# 4-Fuses.net
KiCad netlist of a schematic drawn in Altium Designer
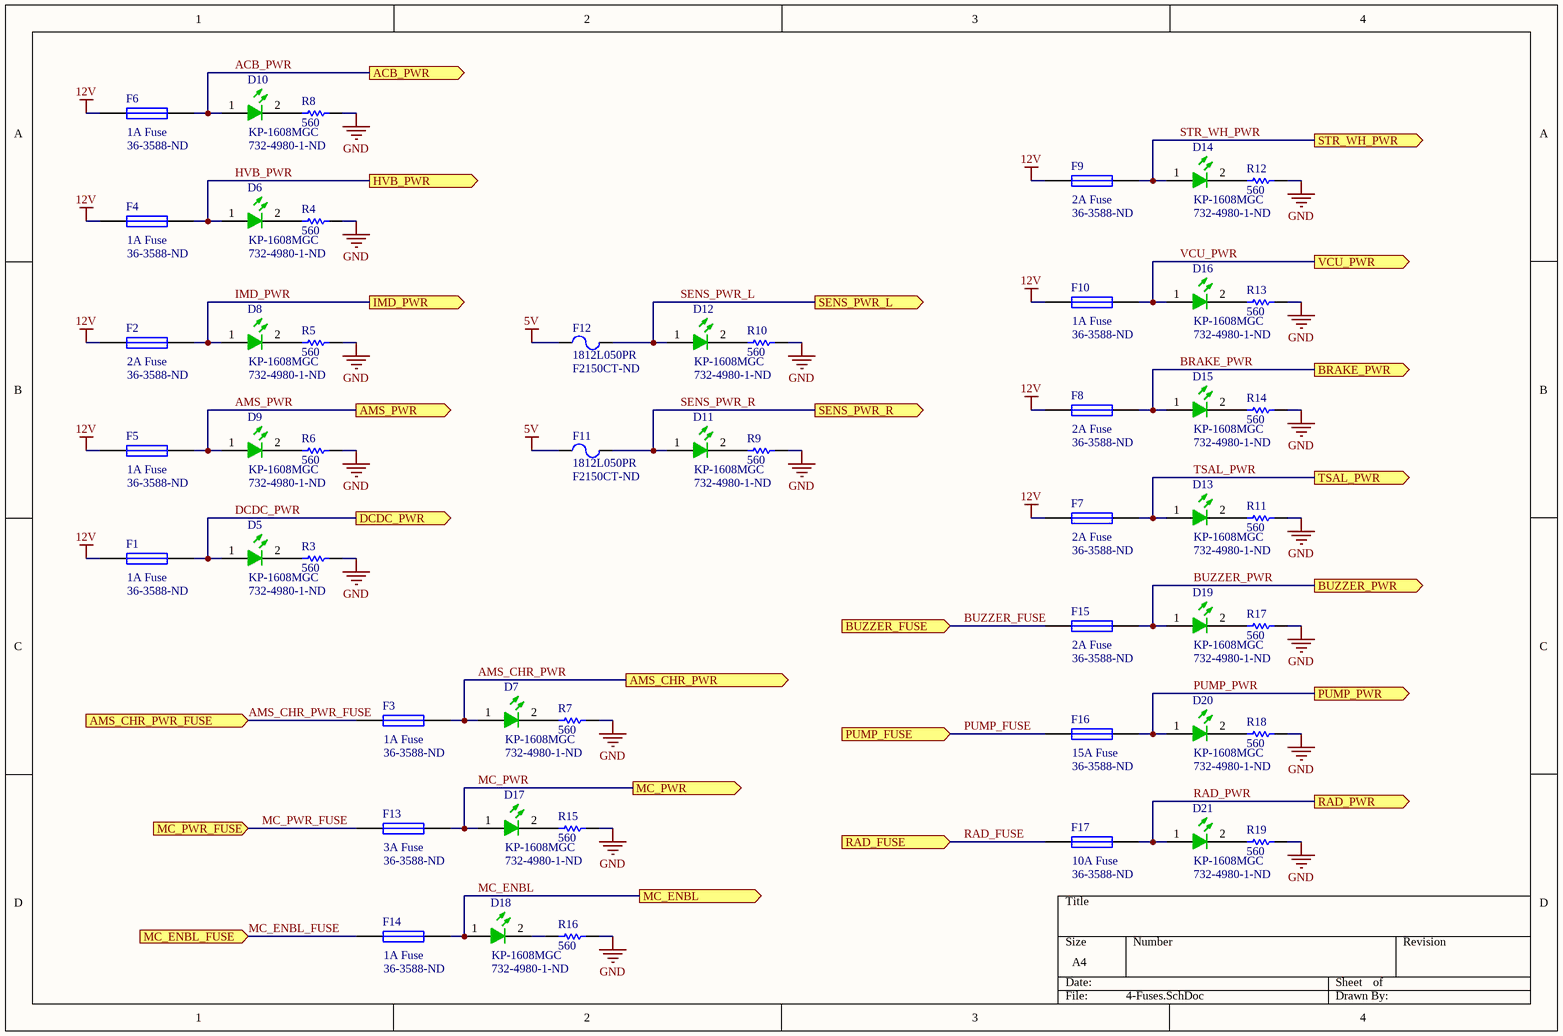
[diagram p0: 4-Fuses.SchDoc]

(export (version "E")
  (design (tool "Eeschema 10.0.6"))
  (components
    (comp (ref "D5")
      (value "KP-1608MGC")
      (footprint "KING-0603LED_GREEN_V")
      (description "LED, SMT, 0603(1608), 1.1mm thickness, Green")
      (fields
        (field (name "MANUFACTURER") "Kingbright")
        (field (name "SUPPLIER PART NUMBER 1") "732-4980-1-ND")
      )
      (libsource (lib "Altium Content Vault") (part "KING-LED-GREEN-A1K2-2"))
    )
    (comp (ref "D6")
      (value "KP-1608MGC")
      (footprint "KING-0603LED_GREEN_V")
      (description "LED, SMT, 0603(1608), 1.1mm thickness, Green")
      (fields
        (field (name "MANUFACTURER") "Kingbright")
        (field (name "SUPPLIER PART NUMBER 1") "732-4980-1-ND")
      )
      (libsource (lib "Altium Content Vault") (part "KING-LED-GREEN-A1K2-2"))
    )
    (comp (ref "D7")
      (value "KP-1608MGC")
      (footprint "KING-0603LED_GREEN_V")
      (description "LED, SMT, 0603(1608), 1.1mm thickness, Green")
      (fields
        (field (name "MANUFACTURER") "Kingbright")
        (field (name "SUPPLIER PART NUMBER 1") "732-4980-1-ND")
      )
      (libsource (lib "Altium Content Vault") (part "KING-LED-GREEN-A1K2-2"))
    )
    (comp (ref "D8")
      (value "KP-1608MGC")
      (footprint "KING-0603LED_GREEN_V")
      (description "LED, SMT, 0603(1608), 1.1mm thickness, Green")
      (fields
        (field (name "MANUFACTURER") "Kingbright")
        (field (name "SUPPLIER PART NUMBER 1") "732-4980-1-ND")
      )
      (libsource (lib "Altium Content Vault") (part "KING-LED-GREEN-A1K2-2"))
    )
    (comp (ref "D9")
      (value "KP-1608MGC")
      (footprint "KING-0603LED_GREEN_V")
      (description "LED, SMT, 0603(1608), 1.1mm thickness, Green")
      (fields
        (field (name "MANUFACTURER") "Kingbright")
        (field (name "SUPPLIER PART NUMBER 1") "732-4980-1-ND")
      )
      (libsource (lib "Altium Content Vault") (part "KING-LED-GREEN-A1K2-2"))
    )
    (comp (ref "D10")
      (value "KP-1608MGC")
      (footprint "KING-0603LED_GREEN_V")
      (description "LED, SMT, 0603(1608), 1.1mm thickness, Green")
      (fields
        (field (name "MANUFACTURER") "Kingbright")
        (field (name "SUPPLIER PART NUMBER 1") "732-4980-1-ND")
      )
      (libsource (lib "Altium Content Vault") (part "KING-LED-GREEN-A1K2-2"))
    )
    (comp (ref "D11")
      (value "KP-1608MGC")
      (footprint "KING-0603LED_GREEN_V")
      (description "LED, SMT, 0603(1608), 1.1mm thickness, Green")
      (fields
        (field (name "MANUFACTURER") "Kingbright")
        (field (name "SUPPLIER PART NUMBER 1") "732-4980-1-ND")
      )
      (libsource (lib "Altium Content Vault") (part "KING-LED-GREEN-A1K2-2"))
    )
    (comp (ref "D12")
      (value "KP-1608MGC")
      (footprint "KING-0603LED_GREEN_V")
      (description "LED, SMT, 0603(1608), 1.1mm thickness, Green")
      (fields
        (field (name "MANUFACTURER") "Kingbright")
        (field (name "SUPPLIER PART NUMBER 1") "732-4980-1-ND")
      )
      (libsource (lib "Altium Content Vault") (part "KING-LED-GREEN-A1K2-2"))
    )
    (comp (ref "D13")
      (value "KP-1608MGC")
      (footprint "KING-0603LED_GREEN_V")
      (description "LED, SMT, 0603(1608), 1.1mm thickness, Green")
      (fields
        (field (name "MANUFACTURER") "Kingbright")
        (field (name "SUPPLIER PART NUMBER 1") "732-4980-1-ND")
      )
      (libsource (lib "Altium Content Vault") (part "KING-LED-GREEN-A1K2-2"))
    )
    (comp (ref "D14")
      (value "KP-1608MGC")
      (footprint "KING-0603LED_GREEN_V")
      (description "LED, SMT, 0603(1608), 1.1mm thickness, Green")
      (fields
        (field (name "MANUFACTURER") "Kingbright")
        (field (name "SUPPLIER PART NUMBER 1") "732-4980-1-ND")
      )
      (libsource (lib "Altium Content Vault") (part "KING-LED-GREEN-A1K2-2"))
    )
    (comp (ref "D15")
      (value "KP-1608MGC")
      (footprint "KING-0603LED_GREEN_V")
      (description "LED, SMT, 0603(1608), 1.1mm thickness, Green")
      (fields
        (field (name "MANUFACTURER") "Kingbright")
        (field (name "SUPPLIER PART NUMBER 1") "732-4980-1-ND")
      )
      (libsource (lib "Altium Content Vault") (part "KING-LED-GREEN-A1K2-2"))
    )
    (comp (ref "D16")
      (value "KP-1608MGC")
      (footprint "KING-0603LED_GREEN_V")
      (description "LED, SMT, 0603(1608), 1.1mm thickness, Green")
      (fields
        (field (name "MANUFACTURER") "Kingbright")
        (field (name "SUPPLIER PART NUMBER 1") "732-4980-1-ND")
      )
      (libsource (lib "Altium Content Vault") (part "KING-LED-GREEN-A1K2-2"))
    )
    (comp (ref "D17")
      (value "KP-1608MGC")
      (footprint "KING-0603LED_GREEN_V")
      (description "LED, SMT, 0603(1608), 1.1mm thickness, Green")
      (fields
        (field (name "MANUFACTURER") "Kingbright")
        (field (name "SUPPLIER PART NUMBER 1") "732-4980-1-ND")
      )
      (libsource (lib "Altium Content Vault") (part "KING-LED-GREEN-A1K2-2"))
    )
    (comp (ref "D18")
      (value "KP-1608MGC")
      (footprint "KING-0603LED_GREEN_V")
      (description "LED, SMT, 0603(1608), 1.1mm thickness, Green")
      (fields
        (field (name "MANUFACTURER") "Kingbright")
        (field (name "SUPPLIER PART NUMBER 1") "732-4980-1-ND")
      )
      (libsource (lib "Altium Content Vault") (part "KING-LED-GREEN-A1K2-2"))
    )
    (comp (ref "D19")
      (value "KP-1608MGC")
      (footprint "KING-0603LED_GREEN_V")
      (description "LED, SMT, 0603(1608), 1.1mm thickness, Green")
      (fields
        (field (name "MANUFACTURER") "Kingbright")
        (field (name "SUPPLIER PART NUMBER 1") "732-4980-1-ND")
      )
      (libsource (lib "Altium Content Vault") (part "KING-LED-GREEN-A1K2-2"))
    )
    (comp (ref "D20")
      (value "KP-1608MGC")
      (footprint "KING-0603LED_GREEN_V")
      (description "LED, SMT, 0603(1608), 1.1mm thickness, Green")
      (fields
        (field (name "MANUFACTURER") "Kingbright")
        (field (name "SUPPLIER PART NUMBER 1") "732-4980-1-ND")
      )
      (libsource (lib "Altium Content Vault") (part "KING-LED-GREEN-A1K2-2"))
    )
    (comp (ref "D21")
      (value "KP-1608MGC")
      (footprint "KING-0603LED_GREEN_V")
      (description "LED, SMT, 0603(1608), 1.1mm thickness, Green")
      (fields
        (field (name "MANUFACTURER") "Kingbright")
        (field (name "SUPPLIER PART NUMBER 1") "732-4980-1-ND")
      )
      (libsource (lib "Altium Content Vault") (part "KING-LED-GREEN-A1K2-2"))
    )
    (comp (ref "F1")
      (value "1A Fuse")
      (footprint "FUSE 3588 Holder")
      (description "Fuse")
      (fields
        (field (name "SUPPLIER PART NUMBER 1") "36-3588-ND")
        (field (name "PUBLISHER") "Altium Limited")
      )
      (libsource (lib "Power_PCB") (part "Fuse 1"))
    )
    (comp (ref "F2")
      (value "2A Fuse")
      (footprint "FUSE 3588 Holder")
      (description "Fuse")
      (fields
        (field (name "SUPPLIER PART NUMBER 1") "36-3588-ND")
        (field (name "PUBLISHER") "Altium Limited")
      )
      (libsource (lib "Power_PCB") (part "Fuse 1"))
    )
    (comp (ref "F3")
      (value "1A Fuse")
      (footprint "FUSE 3588 Holder")
      (description "Fuse")
      (fields
        (field (name "SUPPLIER PART NUMBER 1") "36-3588-ND")
        (field (name "PUBLISHER") "Altium Limited")
      )
      (libsource (lib "Power_PCB") (part "Fuse 1"))
    )
    (comp (ref "F4")
      (value "1A Fuse")
      (footprint "FUSE 3588 Holder")
      (description "Fuse")
      (fields
        (field (name "SUPPLIER PART NUMBER 1") "36-3588-ND")
        (field (name "PUBLISHER") "Altium Limited")
      )
      (libsource (lib "Power_PCB") (part "Fuse 1"))
    )
    (comp (ref "F5")
      (value "1A Fuse")
      (footprint "FUSE 3588 Holder")
      (description "Fuse")
      (fields
        (field (name "SUPPLIER PART NUMBER 1") "36-3588-ND")
        (field (name "PUBLISHER") "Altium Limited")
      )
      (libsource (lib "Power_PCB") (part "Fuse 1"))
    )
    (comp (ref "F6")
      (value "1A Fuse")
      (footprint "FUSE 3588 Holder")
      (description "Fuse")
      (fields
        (field (name "SUPPLIER PART NUMBER 1") "36-3588-ND")
        (field (name "PUBLISHER") "Altium Limited")
      )
      (libsource (lib "Power_PCB") (part "Fuse 1"))
    )
    (comp (ref "F7")
      (value "2A Fuse")
      (footprint "FUSE 3588 Holder")
      (description "Fuse")
      (fields
        (field (name "SUPPLIER PART NUMBER 1") "36-3588-ND")
        (field (name "PUBLISHER") "Altium Limited")
      )
      (libsource (lib "Power_PCB") (part "Fuse 1"))
    )
    (comp (ref "F8")
      (value "2A Fuse")
      (footprint "FUSE 3588 Holder")
      (description "Fuse")
      (fields
        (field (name "SUPPLIER PART NUMBER 1") "36-3588-ND")
        (field (name "PUBLISHER") "Altium Limited")
      )
      (libsource (lib "Power_PCB") (part "Fuse 1"))
    )
    (comp (ref "F9")
      (value "2A Fuse")
      (footprint "FUSE 3588 Holder")
      (description "Fuse")
      (fields
        (field (name "SUPPLIER PART NUMBER 1") "36-3588-ND")
        (field (name "PUBLISHER") "Altium Limited")
      )
      (libsource (lib "Power_PCB") (part "Fuse 1"))
    )
    (comp (ref "F10")
      (value "1A Fuse")
      (footprint "FUSE 3588 Holder")
      (description "Fuse")
      (fields
        (field (name "SUPPLIER PART NUMBER 1") "36-3588-ND")
        (field (name "PUBLISHER") "Altium Limited")
      )
      (libsource (lib "Power_PCB") (part "Fuse 1"))
    )
    (comp (ref "F11")
      (value "1812L050PR")
      (footprint "LFUS-1812L050_V")
      (fields (field (name "TOLERANCE") "1%") (field (name "SUPPLIER PART NUMBER 1") "F2150CT-ND"))
      (libsource (lib "Power_PCB") (part "CMP-1700-00002-1"))
    )
    (comp (ref "F12")
      (value "1812L050PR")
      (footprint "LFUS-1812L050_V")
      (fields (field (name "TOLERANCE") "1%") (field (name "SUPPLIER PART NUMBER 1") "F2150CT-ND"))
      (libsource (lib "Power_PCB") (part "CMP-1700-00002-1"))
    )
    (comp (ref "F13")
      (value "3A Fuse")
      (footprint "FUSE 3588 Holder")
      (description "Fuse")
      (fields
        (field (name "SUPPLIER PART NUMBER 1") "36-3588-ND")
        (field (name "PUBLISHER") "Altium Limited")
      )
      (libsource (lib "Power_PCB") (part "Fuse 1"))
    )
    (comp (ref "F14")
      (value "1A Fuse")
      (footprint "FUSE 3588 Holder")
      (description "Fuse")
      (fields
        (field (name "SUPPLIER PART NUMBER 1") "36-3588-ND")
        (field (name "PUBLISHER") "Altium Limited")
      )
      (libsource (lib "Power_PCB") (part "Fuse 1"))
    )
    (comp (ref "F15")
      (value "2A Fuse")
      (footprint "FUSE 3588 Holder")
      (description "Fuse")
      (fields
        (field (name "SUPPLIER PART NUMBER 1") "36-3588-ND")
        (field (name "PUBLISHER") "Altium Limited")
      )
      (libsource (lib "Power_PCB") (part "Fuse 1"))
    )
    (comp (ref "F16")
      (value "15A Fuse")
      (footprint "FUSE 3588 Holder")
      (description "Fuse")
      (fields
        (field (name "SUPPLIER PART NUMBER 1") "36-3588-ND")
        (field (name "PUBLISHER") "Altium Limited")
      )
      (libsource (lib "Power_PCB") (part "Fuse 1"))
    )
    (comp (ref "F17")
      (value "10A Fuse")
      (footprint "FUSE 3588 Holder")
      (description "Fuse")
      (fields
        (field (name "SUPPLIER PART NUMBER 1") "36-3588-ND")
        (field (name "PUBLISHER") "Altium Limited")
      )
      (libsource (lib "Power_PCB") (part "Fuse 1"))
    )
    (comp (ref "R3")
      (value "560")
      (footprint "RESC0603(1608)_L")
      (description "0603 (1608 Metric) Chip Resistor")
      (libsource (lib "Altium Content Vault") (part "RES_3"))
    )
    (comp (ref "R4")
      (value "560")
      (footprint "RESC0603(1608)_L")
      (description "0603 (1608 Metric) Chip Resistor")
      (libsource (lib "Altium Content Vault") (part "RES_3"))
    )
    (comp (ref "R5")
      (value "560")
      (footprint "RESC0603(1608)_L")
      (description "0603 (1608 Metric) Chip Resistor")
      (libsource (lib "Altium Content Vault") (part "RES_3"))
    )
    (comp (ref "R6")
      (value "560")
      (footprint "RESC0603(1608)_L")
      (description "0603 (1608 Metric) Chip Resistor")
      (libsource (lib "Altium Content Vault") (part "RES_3"))
    )
    (comp (ref "R7")
      (value "560")
      (footprint "RESC0603(1608)_L")
      (description "0603 (1608 Metric) Chip Resistor")
      (libsource (lib "Altium Content Vault") (part "RES_3"))
    )
    (comp (ref "R8")
      (value "560")
      (footprint "RESC0603(1608)_L")
      (description "0603 (1608 Metric) Chip Resistor")
      (libsource (lib "Altium Content Vault") (part "RES_3"))
    )
    (comp (ref "R9")
      (value "560")
      (footprint "RESC0603(1608)_L")
      (description "0603 (1608 Metric) Chip Resistor")
      (libsource (lib "Altium Content Vault") (part "RES_3"))
    )
    (comp (ref "R10")
      (value "560")
      (footprint "RESC0603(1608)_L")
      (description "0603 (1608 Metric) Chip Resistor")
      (libsource (lib "Altium Content Vault") (part "RES_3"))
    )
    (comp (ref "R11")
      (value "560")
      (footprint "RESC0603(1608)_L")
      (description "0603 (1608 Metric) Chip Resistor")
      (libsource (lib "Altium Content Vault") (part "RES_3"))
    )
    (comp (ref "R12")
      (value "560")
      (footprint "RESC0603(1608)_L")
      (description "0603 (1608 Metric) Chip Resistor")
      (libsource (lib "Altium Content Vault") (part "RES_3"))
    )
    (comp (ref "R13")
      (value "560")
      (footprint "RESC0603(1608)_L")
      (description "0603 (1608 Metric) Chip Resistor")
      (libsource (lib "Altium Content Vault") (part "RES_3"))
    )
    (comp (ref "R14")
      (value "560")
      (footprint "RESC0603(1608)_L")
      (description "0603 (1608 Metric) Chip Resistor")
      (libsource (lib "Altium Content Vault") (part "RES_3"))
    )
    (comp (ref "R15")
      (value "560")
      (footprint "RESC0603(1608)_L")
      (description "0603 (1608 Metric) Chip Resistor")
      (libsource (lib "Altium Content Vault") (part "RES_3"))
    )
    (comp (ref "R16")
      (value "560")
      (footprint "RESC0603(1608)_L")
      (description "0603 (1608 Metric) Chip Resistor")
      (libsource (lib "Altium Content Vault") (part "RES_3"))
    )
    (comp (ref "R17")
      (value "560")
      (footprint "RESC0603(1608)_L")
      (description "0603 (1608 Metric) Chip Resistor")
      (libsource (lib "Altium Content Vault") (part "RES_3"))
    )
    (comp (ref "R18")
      (value "560")
      (footprint "RESC0603(1608)_L")
      (description "0603 (1608 Metric) Chip Resistor")
      (libsource (lib "Altium Content Vault") (part "RES_3"))
    )
    (comp (ref "R19")
      (value "560")
      (footprint "RESC0603(1608)_L")
      (description "0603 (1608 Metric) Chip Resistor")
      (libsource (lib "Altium Content Vault") (part "RES_3"))
    )
  )
  (nets
    (net (code "1") (name "/ACB_PWR") (class "Default")
      (node (ref "D10") (pin "1") (pinfunction "A_1") (pintype "passive"))
      (node (ref "F6") (pin "2") (pinfunction "2_2") (pintype "passive"))
    )
    (net (code "2") (name "/AMS_CHR_PWR") (class "Default")
      (node (ref "D7") (pin "1") (pinfunction "A_1") (pintype "passive"))
      (node (ref "F3") (pin "2") (pinfunction "2_2") (pintype "passive"))
    )
    (net (code "3") (name "/AMS_CHR_PWR_FUSE") (class "Default")
      (node (ref "F3") (pin "1") (pinfunction "1_1") (pintype "passive"))
    )
    (net (code "4") (name "/AMS_PWR") (class "Default")
      (node (ref "D9") (pin "1") (pinfunction "A_1") (pintype "passive"))
      (node (ref "F5") (pin "2") (pinfunction "2_2") (pintype "passive"))
    )
    (net (code "5") (name "/BRAKE_PWR") (class "Default")
      (node (ref "D15") (pin "1") (pinfunction "A_1") (pintype "passive"))
      (node (ref "F8") (pin "2") (pinfunction "2_2") (pintype "passive"))
    )
    (net (code "6") (name "/BUZZER_FUSE") (class "Default")
      (node (ref "F15") (pin "1") (pinfunction "1_1") (pintype "passive"))
    )
    (net (code "7") (name "/BUZZER_PWR") (class "Default")
      (node (ref "D19") (pin "1") (pinfunction "A_1") (pintype "passive"))
      (node (ref "F15") (pin "2") (pinfunction "2_2") (pintype "passive"))
    )
    (net (code "8") (name "/DCDC_PWR") (class "Default")
      (node (ref "D5") (pin "1") (pinfunction "A_1") (pintype "passive"))
      (node (ref "F1") (pin "2") (pinfunction "2_2") (pintype "passive"))
    )
    (net (code "9") (name "/HVB_PWR") (class "Default")
      (node (ref "D6") (pin "1") (pinfunction "A_1") (pintype "passive"))
      (node (ref "F4") (pin "2") (pinfunction "2_2") (pintype "passive"))
    )
    (net (code "10") (name "/IMD_PWR") (class "Default")
      (node (ref "D8") (pin "1") (pinfunction "A_1") (pintype "passive"))
      (node (ref "F2") (pin "2") (pinfunction "2_2") (pintype "passive"))
    )
    (net (code "11") (name "/MC_ENBL") (class "Default")
      (node (ref "D18") (pin "1") (pinfunction "A_1") (pintype "passive"))
      (node (ref "F14") (pin "2") (pinfunction "2_2") (pintype "passive"))
    )
    (net (code "12") (name "/MC_ENBL_FUSE") (class "Default")
      (node (ref "F14") (pin "1") (pinfunction "1_1") (pintype "passive"))
    )
    (net (code "13") (name "/MC_PWR") (class "Default")
      (node (ref "D17") (pin "1") (pinfunction "A_1") (pintype "passive"))
      (node (ref "F13") (pin "2") (pinfunction "2_2") (pintype "passive"))
    )
    (net (code "14") (name "/MC_PWR_FUSE") (class "Default")
      (node (ref "F13") (pin "1") (pinfunction "1_1") (pintype "passive"))
    )
    (net (code "15") (name "/PUMP_FUSE") (class "Default")
      (node (ref "F16") (pin "1") (pinfunction "1_1") (pintype "passive"))
    )
    (net (code "16") (name "/PUMP_PWR") (class "Default")
      (node (ref "D20") (pin "1") (pinfunction "A_1") (pintype "passive"))
      (node (ref "F16") (pin "2") (pinfunction "2_2") (pintype "passive"))
    )
    (net (code "17") (name "/RAD_FUSE") (class "Default")
      (node (ref "F17") (pin "1") (pinfunction "1_1") (pintype "passive"))
    )
    (net (code "18") (name "/RAD_PWR") (class "Default")
      (node (ref "D21") (pin "1") (pinfunction "A_1") (pintype "passive"))
      (node (ref "F17") (pin "2") (pinfunction "2_2") (pintype "passive"))
    )
    (net (code "19") (name "/SENS_PWR_L") (class "Default")
      (node (ref "D12") (pin "1") (pinfunction "A_1") (pintype "passive"))
      (node (ref "F12") (pin "2") (pinfunction "2_2") (pintype "passive"))
    )
    (net (code "20") (name "/SENS_PWR_R") (class "Default")
      (node (ref "D11") (pin "1") (pinfunction "A_1") (pintype "passive"))
      (node (ref "F11") (pin "2") (pinfunction "2_2") (pintype "passive"))
    )
    (net (code "21") (name "/STR_WH_PWR") (class "Default")
      (node (ref "D14") (pin "1") (pinfunction "A_1") (pintype "passive"))
      (node (ref "F9") (pin "2") (pinfunction "2_2") (pintype "passive"))
    )
    (net (code "22") (name "/TSAL_PWR") (class "Default")
      (node (ref "D13") (pin "1") (pinfunction "A_1") (pintype "passive"))
      (node (ref "F7") (pin "2") (pinfunction "2_2") (pintype "passive"))
    )
    (net (code "23") (name "/VCU_PWR") (class "Default")
      (node (ref "D16") (pin "1") (pinfunction "A_1") (pintype "passive"))
      (node (ref "F10") (pin "2") (pinfunction "2_2") (pintype "passive"))
    )
    (net (code "24") (name "5V") (class "Default")
      (node (ref "F11") (pin "1") (pinfunction "1_1") (pintype "passive"))
      (node (ref "F12") (pin "1") (pinfunction "1_1") (pintype "passive"))
    )
    (net (code "25") (name "12V") (class "Default")
      (node (ref "F1") (pin "1") (pinfunction "1_1") (pintype "passive"))
      (node (ref "F10") (pin "1") (pinfunction "1_1") (pintype "passive"))
      (node (ref "F2") (pin "1") (pinfunction "1_1") (pintype "passive"))
      (node (ref "F4") (pin "1") (pinfunction "1_1") (pintype "passive"))
      (node (ref "F5") (pin "1") (pinfunction "1_1") (pintype "passive"))
      (node (ref "F6") (pin "1") (pinfunction "1_1") (pintype "passive"))
      (node (ref "F7") (pin "1") (pinfunction "1_1") (pintype "passive"))
      (node (ref "F8") (pin "1") (pinfunction "1_1") (pintype "passive"))
      (node (ref "F9") (pin "1") (pinfunction "1_1") (pintype "passive"))
    )
    (net (code "26") (name "GND") (class "Default")
      (node (ref "R10") (pin "2") (pinfunction "2_2") (pintype "passive"))
      (node (ref "R11") (pin "2") (pinfunction "2_2") (pintype "passive"))
      (node (ref "R12") (pin "2") (pinfunction "2_2") (pintype "passive"))
      (node (ref "R13") (pin "2") (pinfunction "2_2") (pintype "passive"))
      (node (ref "R14") (pin "2") (pinfunction "2_2") (pintype "passive"))
      (node (ref "R15") (pin "2") (pinfunction "2_2") (pintype "passive"))
      (node (ref "R16") (pin "2") (pinfunction "2_2") (pintype "passive"))
      (node (ref "R17") (pin "2") (pinfunction "2_2") (pintype "passive"))
      (node (ref "R18") (pin "2") (pinfunction "2_2") (pintype "passive"))
      (node (ref "R19") (pin "2") (pinfunction "2_2") (pintype "passive"))
      (node (ref "R3") (pin "2") (pinfunction "2_2") (pintype "passive"))
      (node (ref "R4") (pin "2") (pinfunction "2_2") (pintype "passive"))
      (node (ref "R5") (pin "2") (pinfunction "2_2") (pintype "passive"))
      (node (ref "R6") (pin "2") (pinfunction "2_2") (pintype "passive"))
      (node (ref "R7") (pin "2") (pinfunction "2_2") (pintype "passive"))
      (node (ref "R8") (pin "2") (pinfunction "2_2") (pintype "passive"))
      (node (ref "R9") (pin "2") (pinfunction "2_2") (pintype "passive"))
    )
    (net (code "27") (name "Net-(D5-K)") (class "Default")
      (node (ref "D5") (pin "2") (pinfunction "K_2") (pintype "passive"))
      (node (ref "R3") (pin "1") (pinfunction "1_1") (pintype "passive"))
    )
    (net (code "28") (name "Net-(D6-K)") (class "Default")
      (node (ref "D6") (pin "2") (pinfunction "K_2") (pintype "passive"))
      (node (ref "R4") (pin "1") (pinfunction "1_1") (pintype "passive"))
    )
    (net (code "29") (name "Net-(D7-K)") (class "Default")
      (node (ref "D7") (pin "2") (pinfunction "K_2") (pintype "passive"))
      (node (ref "R7") (pin "1") (pinfunction "1_1") (pintype "passive"))
    )
    (net (code "30") (name "Net-(D8-K)") (class "Default")
      (node (ref "D8") (pin "2") (pinfunction "K_2") (pintype "passive"))
      (node (ref "R5") (pin "1") (pinfunction "1_1") (pintype "passive"))
    )
    (net (code "31") (name "Net-(D9-K)") (class "Default")
      (node (ref "D9") (pin "2") (pinfunction "K_2") (pintype "passive"))
      (node (ref "R6") (pin "1") (pinfunction "1_1") (pintype "passive"))
    )
    (net (code "32") (name "Net-(D10-K)") (class "Default")
      (node (ref "D10") (pin "2") (pinfunction "K_2") (pintype "passive"))
      (node (ref "R8") (pin "1") (pinfunction "1_1") (pintype "passive"))
    )
    (net (code "33") (name "Net-(D11-K)") (class "Default")
      (node (ref "D11") (pin "2") (pinfunction "K_2") (pintype "passive"))
      (node (ref "R9") (pin "1") (pinfunction "1_1") (pintype "passive"))
    )
    (net (code "34") (name "Net-(D12-K)") (class "Default")
      (node (ref "D12") (pin "2") (pinfunction "K_2") (pintype "passive"))
      (node (ref "R10") (pin "1") (pinfunction "1_1") (pintype "passive"))
    )
    (net (code "35") (name "Net-(D13-K)") (class "Default")
      (node (ref "D13") (pin "2") (pinfunction "K_2") (pintype "passive"))
      (node (ref "R11") (pin "1") (pinfunction "1_1") (pintype "passive"))
    )
    (net (code "36") (name "Net-(D14-K)") (class "Default")
      (node (ref "D14") (pin "2") (pinfunction "K_2") (pintype "passive"))
      (node (ref "R12") (pin "1") (pinfunction "1_1") (pintype "passive"))
    )
    (net (code "37") (name "Net-(D15-K)") (class "Default")
      (node (ref "D15") (pin "2") (pinfunction "K_2") (pintype "passive"))
      (node (ref "R14") (pin "1") (pinfunction "1_1") (pintype "passive"))
    )
    (net (code "38") (name "Net-(D16-K)") (class "Default")
      (node (ref "D16") (pin "2") (pinfunction "K_2") (pintype "passive"))
      (node (ref "R13") (pin "1") (pinfunction "1_1") (pintype "passive"))
    )
    (net (code "39") (name "Net-(D17-K)") (class "Default")
      (node (ref "D17") (pin "2") (pinfunction "K_2") (pintype "passive"))
      (node (ref "R15") (pin "1") (pinfunction "1_1") (pintype "passive"))
    )
    (net (code "40") (name "Net-(D18-K)") (class "Default")
      (node (ref "D18") (pin "2") (pinfunction "K_2") (pintype "passive"))
      (node (ref "R16") (pin "1") (pinfunction "1_1") (pintype "passive"))
    )
    (net (code "41") (name "Net-(D19-K)") (class "Default")
      (node (ref "D19") (pin "2") (pinfunction "K_2") (pintype "passive"))
      (node (ref "R17") (pin "1") (pinfunction "1_1") (pintype "passive"))
    )
    (net (code "42") (name "Net-(D20-K)") (class "Default")
      (node (ref "D20") (pin "2") (pinfunction "K_2") (pintype "passive"))
      (node (ref "R18") (pin "1") (pinfunction "1_1") (pintype "passive"))
    )
    (net (code "43") (name "Net-(D21-K)") (class "Default")
      (node (ref "D21") (pin "2") (pinfunction "K_2") (pintype "passive"))
      (node (ref "R19") (pin "1") (pinfunction "1_1") (pintype "passive"))
    )
  )
)
